# SSR.net
KiCad netlist of a schematic drawn in Altium Designer
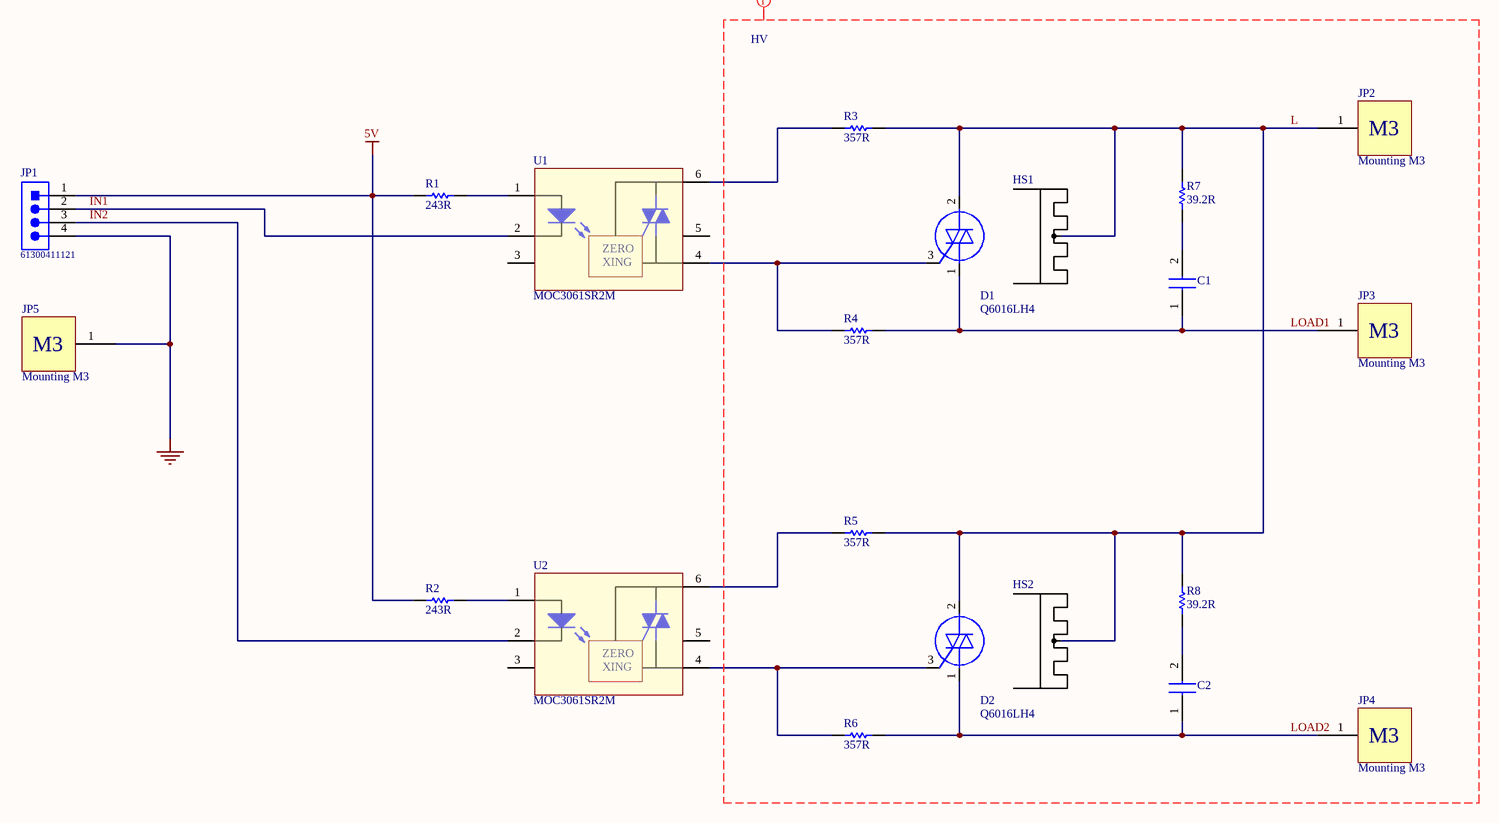
[diagram p0: SSR.SchDoc]

(export (version "E")
  (design (tool "Eeschema 10.0.6"))
  (components
    (comp (ref "C1")
      (value "C1210C103JBTACAUTO")
      (footprint "SSR:CAPC3225X140N")
      (description "Capacitor")
      (fields (field (name "MOUSER PART NUMBER") "80-C1210C103JBTAUTO"))
      (libsource (lib "SSR") (part "C1210C103JBTACAUTO"))
    )
    (comp (ref "C2")
      (value "C1210C103JBTACAUTO")
      (footprint "SSR:CAPC3225X140N")
      (description "Capacitor")
      (fields (field (name "MOUSER PART NUMBER") "80-C1210C103JBTAUTO"))
      (libsource (lib "SSR") (part "C1210C103JBTACAUTO"))
    )
    (comp (ref "D1")
      (value "Q6016LH4")
      (footprint "SSR:TO254P478X1016X1956-3P")
      (description "Thyristor")
      (libsource (lib "SSR") (part "Q6016LH4"))
    )
    (comp (ref "D2")
      (value "Q6016LH4")
      (footprint "SSR:TO254P478X1016X1956-3P")
      (description "Thyristor")
      (libsource (lib "SSR") (part "Q6016LH4"))
    )
    (comp (ref "HS1")
      (value "HeatsinkTO220")
      (footprint "HeatsinkTO220")
      (description "Simple model for a cheap Aliexpress 20*15*11 TO-220 pure aluminium heat sink")
      (libsource (lib "MUAB_Altium_Lib") (part "HeatsinkTO220"))
    )
    (comp (ref "HS2")
      (value "HeatsinkTO220")
      (footprint "HeatsinkTO220")
      (description "Simple model for a cheap Aliexpress 20*15*11 TO-220 pure aluminium heat sink")
      (libsource (lib "MUAB_Altium_Lib") (part "HeatsinkTO220"))
    )
    (comp (ref "JP1")
      (value "61300411121")
      (footprint "61300411121")
      (description "WR-PHD Pin Header, THT, pitch 2.54mm, Single Row, Vertical, 4p")
      (fields (field (name "MANUFACTURER") "Wurth Elektronik"))
      (libsource (lib "Altium_WR-PHD (rev22a)") (part "61300411121"))
    )
    (comp (ref "JP2") (value "Mounting M3") (footprint "M3") (libsource (lib "") (part "CONNM3_1")))
    (comp (ref "JP3") (value "Mounting M3") (footprint "M3") (libsource (lib "") (part "CONNM3_1")))
    (comp (ref "JP4") (value "Mounting M3") (footprint "M3") (libsource (lib "") (part "CONNM3_1")))
    (comp (ref "JP5") (value "Mounting M3") (footprint "M3") (libsource (lib "SSR") (part "CONNM3")))
    (comp (ref "R1")
      (value "243R")
      (footprint "RES_0603_H050 (_IPC_MD)")
      (description "243R 1% 0,1W 75V 0603")
      (fields (field (name "PART NUMBER") "RES243R1%0603"))
      (libsource (lib "MUAB_Altium_Lib") (part "RES"))
    )
    (comp (ref "R2")
      (value "243R")
      (footprint "RES_0603_H050 (_IPC_MD)")
      (description "243R 1% 0,1W 75V 0603")
      (fields (field (name "PART NUMBER") "RES243R1%0603"))
      (libsource (lib "MUAB_Altium_Lib") (part "RES"))
    )
    (comp (ref "R3")
      (value "357R")
      (footprint "RES_1206_H060 (_IPC_MD)")
      (description "357R 1% 0,25W 200V 1206")
      (fields (field (name "PART NUMBER") "RES357R1%1206"))
      (libsource (lib "MUAB_Altium_Lib") (part "RES"))
    )
    (comp (ref "R4")
      (value "357R")
      (footprint "RES_1206_H060 (_IPC_MD)")
      (description "357R 1% 0,25W 200V 1206")
      (fields (field (name "PART NUMBER") "RES357R1%1206"))
      (libsource (lib "MUAB_Altium_Lib") (part "RES"))
    )
    (comp (ref "R5")
      (value "357R")
      (footprint "RES_1206_H060 (_IPC_MD)")
      (description "357R 1% 0,25W 200V 1206")
      (fields (field (name "PART NUMBER") "RES357R1%1206"))
      (libsource (lib "MUAB_Altium_Lib") (part "RES"))
    )
    (comp (ref "R6")
      (value "357R")
      (footprint "RES_1206_H060 (_IPC_MD)")
      (description "357R 1% 0,25W 200V 1206")
      (fields (field (name "PART NUMBER") "RES357R1%1206"))
      (libsource (lib "MUAB_Altium_Lib") (part "RES"))
    )
    (comp (ref "R7")
      (value "39.2R")
      (footprint "RES_1206_H060 (_IPC_MD)")
      (description "39.2R 1% 0,25W 200V 1206")
      (fields (field (name "PART NUMBER") "RES39.2R1%1206"))
      (libsource (lib "MUAB_Altium_Lib") (part "RES"))
    )
    (comp (ref "R8")
      (value "39.2R")
      (footprint "RES_1206_H060 (_IPC_MD)")
      (description "39.2R 1% 0,25W 200V 1206")
      (fields (field (name "PART NUMBER") "RES39.2R1%1206"))
      (libsource (lib "MUAB_Altium_Lib") (part "RES"))
    )
    (comp (ref "U1")
      (value "MOC3061SR2M")
      (footprint "SSR:SOT254P916X508-6N")
      (description "Integrated Circuit")
      (fields (field (name "MOUSER PART NUMBER") "512-MOC3061SR2M"))
      (libsource (lib "SSR") (part "MOC3061SR2M"))
    )
    (comp (ref "U2")
      (value "MOC3061SR2M")
      (footprint "SSR:SOT254P916X508-6N")
      (description "Integrated Circuit")
      (fields (field (name "MOUSER PART NUMBER") "512-MOC3061SR2M"))
      (libsource (lib "SSR") (part "MOC3061SR2M"))
    )
  )
  (nets
    (net (code "1") (name "/IN1") (class "Default")
      (node (ref "JP1") (pin "2") (pinfunction "2_2") (pintype "passive"))
      (node (ref "U1") (pin "2") (pinfunction "K_2") (pintype "passive"))
    )
    (net (code "2") (name "/IN2") (class "Default")
      (node (ref "JP1") (pin "3") (pinfunction "3_3") (pintype "passive"))
      (node (ref "U2") (pin "2") (pinfunction "K_2") (pintype "passive"))
    )
    (net (code "3") (name "/L") (class "Default")
      (node (ref "D1") (pin "2") (pinfunction "MT2_2") (pintype "passive"))
      (node (ref "D2") (pin "2") (pinfunction "MT2_2") (pintype "passive"))
      (node (ref "HS1") (pin "0") (pinfunction "0_0") (pintype "passive"))
      (node (ref "HS2") (pin "0") (pinfunction "0_0") (pintype "passive"))
      (node (ref "JP2") (pin "1") (pinfunction "1_1") (pintype "passive"))
      (node (ref "R3") (pin "2") (pinfunction "2_2") (pintype "passive"))
      (node (ref "R5") (pin "2") (pinfunction "2_2") (pintype "passive"))
      (node (ref "R7") (pin "1") (pinfunction "1_1") (pintype "passive"))
      (node (ref "R8") (pin "1") (pinfunction "1_1") (pintype "passive"))
    )
    (net (code "4") (name "/LOAD1") (class "Default")
      (node (ref "C1") (pin "1") (pinfunction "1_1") (pintype "passive"))
      (node (ref "D1") (pin "1") (pinfunction "MT1_1") (pintype "passive"))
      (node (ref "JP3") (pin "1") (pinfunction "1_1") (pintype "passive"))
      (node (ref "R4") (pin "2") (pinfunction "2_2") (pintype "passive"))
    )
    (net (code "5") (name "/LOAD2") (class "Default")
      (node (ref "C2") (pin "1") (pinfunction "1_1") (pintype "passive"))
      (node (ref "D2") (pin "1") (pinfunction "MT1_1") (pintype "passive"))
      (node (ref "JP4") (pin "1") (pinfunction "1_1") (pintype "passive"))
      (node (ref "R6") (pin "2") (pinfunction "2_2") (pintype "passive"))
    )
    (net (code "6") (name "5V") (class "Default")
      (node (ref "JP1") (pin "1") (pinfunction "1_1") (pintype "passive"))
      (node (ref "R1") (pin "1") (pinfunction "1_1") (pintype "passive"))
      (node (ref "R2") (pin "1") (pinfunction "1_1") (pintype "passive"))
    )
    (net (code "7") (name "GND") (class "Default")
      (node (ref "JP1") (pin "4") (pinfunction "4_4") (pintype "passive"))
      (node (ref "JP5") (pin "1") (pinfunction "1_1") (pintype "passive"))
    )
    (net (code "8") (name "Net-(C1-Pad2)") (class "Default")
      (node (ref "C1") (pin "2") (pinfunction "2_2") (pintype "passive"))
      (node (ref "R7") (pin "2") (pinfunction "2_2") (pintype "passive"))
    )
    (net (code "9") (name "Net-(C2-Pad2)") (class "Default")
      (node (ref "C2") (pin "2") (pinfunction "2_2") (pintype "passive"))
      (node (ref "R8") (pin "2") (pinfunction "2_2") (pintype "passive"))
    )
    (net (code "10") (name "Net-(D1-G)") (class "Default")
      (node (ref "D1") (pin "3") (pinfunction "G_3") (pintype "passive"))
      (node (ref "R4") (pin "1") (pinfunction "1_1") (pintype "passive"))
      (node (ref "U1") (pin "4") (pinfunction "MAIN_TERM._1_4") (pintype "passive"))
    )
    (net (code "11") (name "Net-(D2-G)") (class "Default")
      (node (ref "D2") (pin "3") (pinfunction "G_3") (pintype "passive"))
      (node (ref "R6") (pin "1") (pinfunction "1_1") (pintype "passive"))
      (node (ref "U2") (pin "4") (pinfunction "MAIN_TERM._1_4") (pintype "passive"))
    )
    (net (code "12") (name "Net-(U1-ANODE)") (class "Default")
      (node (ref "R1") (pin "2") (pinfunction "2_2") (pintype "passive"))
      (node (ref "U1") (pin "1") (pinfunction "ANODE_1") (pintype "passive"))
    )
    (net (code "13") (name "Net-(U1-MAIN_TERM._2)") (class "Default")
      (node (ref "R3") (pin "1") (pinfunction "1_1") (pintype "passive"))
      (node (ref "U1") (pin "6") (pinfunction "MAIN_TERM._2_6") (pintype "passive"))
    )
    (net (code "14") (name "Net-(U2-ANODE)") (class "Default")
      (node (ref "R2") (pin "2") (pinfunction "2_2") (pintype "passive"))
      (node (ref "U2") (pin "1") (pinfunction "ANODE_1") (pintype "passive"))
    )
    (net (code "15") (name "Net-(U2-MAIN_TERM._2)") (class "Default")
      (node (ref "R5") (pin "1") (pinfunction "1_1") (pintype "passive"))
      (node (ref "U2") (pin "6") (pinfunction "MAIN_TERM._2_6") (pintype "passive"))
    )
    (net (code "16") (name "unconnected-(U1-NC-Pad5)") (class "Default")
      (node (ref "U1") (pin "5") (pinfunction "NC_5") (pintype "passive"))
    )
    (net (code "17") (name "unconnected-(U1-N{slash}C-Pad3)") (class "Default")
      (node (ref "U1") (pin "3") (pinfunction "N/C_3") (pintype "passive"))
    )
    (net (code "18") (name "unconnected-(U2-NC-Pad5)") (class "Default")
      (node (ref "U2") (pin "5") (pinfunction "NC_5") (pintype "passive"))
    )
    (net (code "19") (name "unconnected-(U2-N{slash}C-Pad3)") (class "Default")
      (node (ref "U2") (pin "3") (pinfunction "N/C_3") (pintype "passive"))
    )
  )
)
